# mp3_Breakout.net
KiCad netlist of a schematic drawn in EAGLE
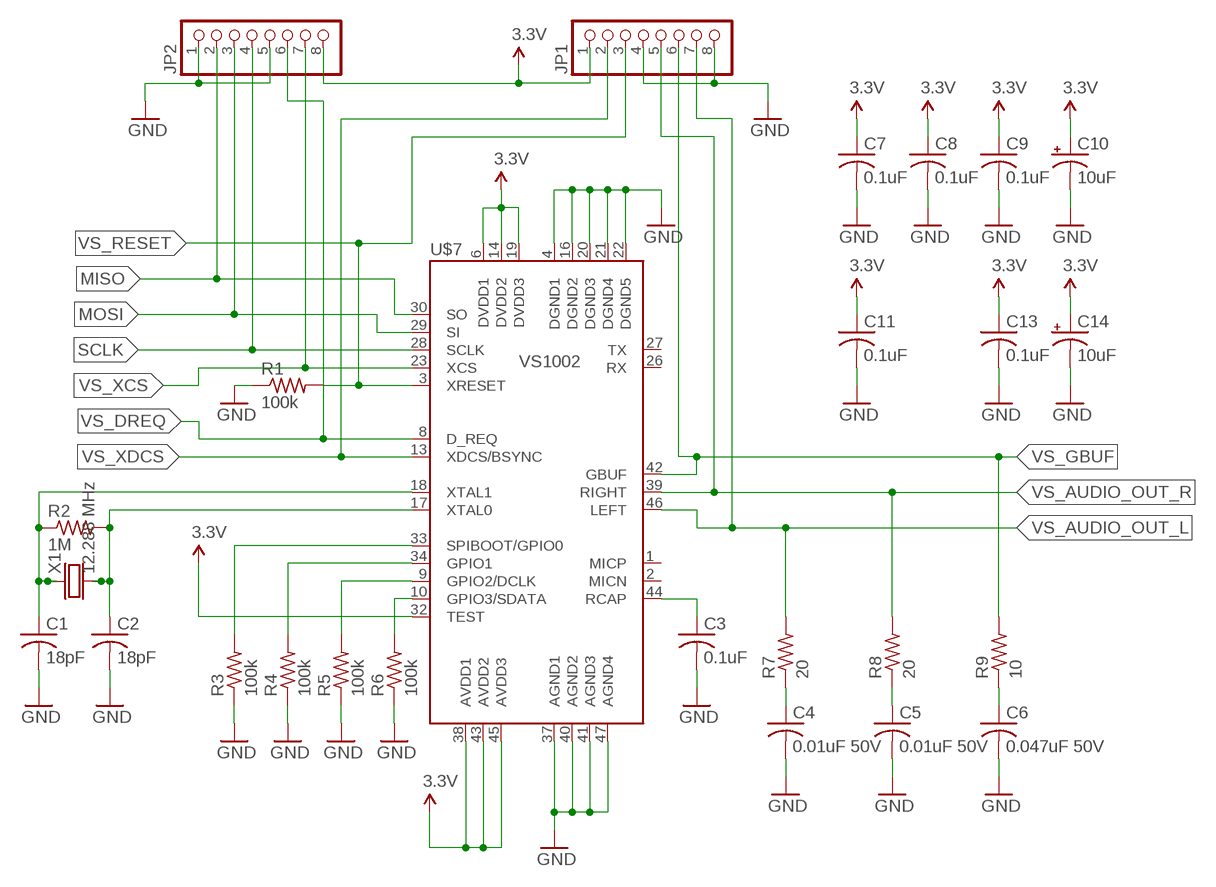
[diagram p0: schematic, sheet 1]

(export (version "E")
  (design (tool "Eeschema 10.0.6"))
  (components
    (comp (ref "C1")
      (value "18pF")
      (footprint "eagle-import:0603_RESISTOR")
      (libsource (lib "eagle-import") (part "0603_CAP"))
    )
    (comp (ref "C2")
      (value "18pF")
      (footprint "eagle-import:0603_RESISTOR")
      (libsource (lib "eagle-import") (part "0603_CAP"))
    )
    (comp (ref "C3")
      (value "0.1uF")
      (footprint "eagle-import:0603_RESISTOR")
      (libsource (lib "eagle-import") (part "0603_CAP"))
    )
    (comp (ref "C4")
      (value "0.01uF 50V")
      (footprint "eagle-import:0603_RESISTOR")
      (libsource (lib "eagle-import") (part "0603_CAP"))
    )
    (comp (ref "C5")
      (value "0.01uF 50V")
      (footprint "eagle-import:0603_RESISTOR")
      (libsource (lib "eagle-import") (part "0603_CAP"))
    )
    (comp (ref "C6")
      (value "0.047uF 50V")
      (footprint "eagle-import:0603_RESISTOR")
      (libsource (lib "eagle-import") (part "0603_CAP"))
    )
    (comp (ref "C7")
      (value "0.1uF")
      (footprint "eagle-import:0603_RESISTOR")
      (libsource (lib "eagle-import") (part "0603_CAP"))
    )
    (comp (ref "C8")
      (value "0.1uF")
      (footprint "eagle-import:0603_RESISTOR")
      (libsource (lib "eagle-import") (part "0603_CAP"))
    )
    (comp (ref "C9")
      (value "0.1uF")
      (footprint "eagle-import:0603_RESISTOR")
      (libsource (lib "eagle-import") (part "0603_CAP"))
    )
    (comp (ref "C10")
      (value "10uF")
      (footprint "eagle-import:CAP_B")
      (libsource (lib "eagle-import") (part "CAP_POL_B"))
    )
    (comp (ref "C11")
      (value "0.1uF")
      (footprint "eagle-import:0603_RESISTOR")
      (libsource (lib "eagle-import") (part "0603_CAP"))
    )
    (comp (ref "C13")
      (value "0.1uF")
      (footprint "eagle-import:0603_RESISTOR")
      (libsource (lib "eagle-import") (part "0603_CAP"))
    )
    (comp (ref "C14")
      (value "10uF")
      (footprint "eagle-import:CAP_B")
      (libsource (lib "eagle-import") (part "CAP_POL_B"))
    )
    (comp (ref "JP1")
      (value "PINHD-1X8")
      (footprint "eagle-import:1X08")
      (libsource (lib "eagle-import") (part "PINHD-1X8"))
    )
    (comp (ref "JP2")
      (value "PINHD-1X8")
      (footprint "eagle-import:1X08")
      (libsource (lib "eagle-import") (part "PINHD-1X8"))
    )
    (comp (ref "R1")
      (value "100k")
      (footprint "eagle-import:0603_RESISTOR")
      (libsource (lib "eagle-import") (part "0603_RESISTOR"))
    )
    (comp (ref "R2")
      (value "1M")
      (footprint "eagle-import:0603_RESISTOR")
      (libsource (lib "eagle-import") (part "0603_RESISTOR"))
    )
    (comp (ref "R3")
      (value "100k")
      (footprint "eagle-import:0603_RESISTOR")
      (libsource (lib "eagle-import") (part "0603_RESISTOR"))
    )
    (comp (ref "R4")
      (value "100k")
      (footprint "eagle-import:0603_RESISTOR")
      (libsource (lib "eagle-import") (part "0603_RESISTOR"))
    )
    (comp (ref "R5")
      (value "100k")
      (footprint "eagle-import:0603_RESISTOR")
      (libsource (lib "eagle-import") (part "0603_RESISTOR"))
    )
    (comp (ref "R6")
      (value "100k")
      (footprint "eagle-import:0603_RESISTOR")
      (libsource (lib "eagle-import") (part "0603_RESISTOR"))
    )
    (comp (ref "R7")
      (value "20")
      (footprint "eagle-import:0603_RESISTOR")
      (libsource (lib "eagle-import") (part "0603_RESISTOR"))
    )
    (comp (ref "R8")
      (value "20")
      (footprint "eagle-import:0603_RESISTOR")
      (libsource (lib "eagle-import") (part "0603_RESISTOR"))
    )
    (comp (ref "R9")
      (value "10")
      (footprint "eagle-import:0603_RESISTOR")
      (libsource (lib "eagle-import") (part "0603_RESISTOR"))
    )
    (comp (ref "U$7")
      (value "VS1002")
      (footprint "eagle-import:LQFP-48")
      (libsource (lib "eagle-import") (part "VS1002"))
    )
    (comp (ref "X1")
      (value "12.288 MHz")
      (footprint "eagle-import:CRYSTAL_5X3")
      (libsource (lib "eagle-import") (part "CRYSTAL_5X3"))
    )
  )
  (nets
    (net (code "1") (name "3.3V") (class "Default")
      (node (ref "C10") (pin "+") (pinfunction "+_+") (pintype "passive"))
      (node (ref "C11") (pin "1") (pinfunction "1_1") (pintype "passive"))
      (node (ref "C13") (pin "1") (pinfunction "1_1") (pintype "passive"))
      (node (ref "C14") (pin "+") (pinfunction "+_+") (pintype "passive"))
      (node (ref "C7") (pin "1") (pinfunction "1_1") (pintype "passive"))
      (node (ref "C8") (pin "1") (pinfunction "1_1") (pintype "passive"))
      (node (ref "C9") (pin "1") (pinfunction "1_1") (pintype "passive"))
      (node (ref "JP1") (pin "1") (pinfunction "1_1") (pintype "passive"))
      (node (ref "JP2") (pin "8") (pinfunction "8_8") (pintype "passive"))
      (node (ref "U$7") (pin "14") (pinfunction "DVDD2_14") (pintype "power_in"))
      (node (ref "U$7") (pin "19") (pinfunction "DVDD3_19") (pintype "power_in"))
      (node (ref "U$7") (pin "32") (pinfunction "TEST_32") (pintype "bidirectional"))
      (node (ref "U$7") (pin "38") (pinfunction "AVDD1_38") (pintype "power_in"))
      (node (ref "U$7") (pin "43") (pinfunction "AVDD2_43") (pintype "power_in"))
      (node (ref "U$7") (pin "45") (pinfunction "AVDD3_45") (pintype "power_in"))
      (node (ref "U$7") (pin "6") (pinfunction "DVDD1_6") (pintype "power_in"))
    )
    (net (code "2") (name "GND") (class "Default")
      (node (ref "C1") (pin "2") (pinfunction "2_2") (pintype "passive"))
      (node (ref "C10") (pin "-") (pinfunction "-_-") (pintype "passive"))
      (node (ref "C11") (pin "2") (pinfunction "2_2") (pintype "passive"))
      (node (ref "C13") (pin "2") (pinfunction "2_2") (pintype "passive"))
      (node (ref "C14") (pin "-") (pinfunction "-_-") (pintype "passive"))
      (node (ref "C2") (pin "2") (pinfunction "2_2") (pintype "passive"))
      (node (ref "C3") (pin "2") (pinfunction "2_2") (pintype "passive"))
      (node (ref "C4") (pin "2") (pinfunction "2_2") (pintype "passive"))
      (node (ref "C5") (pin "2") (pinfunction "2_2") (pintype "passive"))
      (node (ref "C6") (pin "2") (pinfunction "2_2") (pintype "passive"))
      (node (ref "C7") (pin "2") (pinfunction "2_2") (pintype "passive"))
      (node (ref "C8") (pin "2") (pinfunction "2_2") (pintype "passive"))
      (node (ref "C9") (pin "2") (pinfunction "2_2") (pintype "passive"))
      (node (ref "JP1") (pin "4") (pinfunction "4_4") (pintype "passive"))
      (node (ref "JP1") (pin "8") (pinfunction "8_8") (pintype "passive"))
      (node (ref "JP2") (pin "1") (pinfunction "1_1") (pintype "passive"))
      (node (ref "JP2") (pin "5") (pinfunction "5_5") (pintype "passive"))
      (node (ref "R1") (pin "1") (pinfunction "1_1") (pintype "passive"))
      (node (ref "R3") (pin "1") (pinfunction "1_1") (pintype "passive"))
      (node (ref "R4") (pin "1") (pinfunction "1_1") (pintype "passive"))
      (node (ref "R5") (pin "1") (pinfunction "1_1") (pintype "passive"))
      (node (ref "R6") (pin "1") (pinfunction "1_1") (pintype "passive"))
      (node (ref "U$7") (pin "16") (pinfunction "DGND2_16") (pintype "bidirectional"))
      (node (ref "U$7") (pin "20") (pinfunction "DGND3_20") (pintype "bidirectional"))
      (node (ref "U$7") (pin "21") (pinfunction "DGND4_21") (pintype "bidirectional"))
      (node (ref "U$7") (pin "22") (pinfunction "DGND5_22") (pintype "bidirectional"))
      (node (ref "U$7") (pin "37") (pinfunction "AGND1_37") (pintype "bidirectional"))
      (node (ref "U$7") (pin "4") (pinfunction "DGND1_4") (pintype "power_in"))
      (node (ref "U$7") (pin "40") (pinfunction "AGND2_40") (pintype "bidirectional"))
      (node (ref "U$7") (pin "41") (pinfunction "AGND3_41") (pintype "bidirectional"))
      (node (ref "U$7") (pin "47") (pinfunction "AGND4_47") (pintype "bidirectional"))
    )
    (net (code "3") (name "MISO") (class "Default")
      (node (ref "JP2") (pin "2") (pinfunction "2_2") (pintype "passive"))
      (node (ref "U$7") (pin "30") (pinfunction "SO_30") (pintype "bidirectional"))
    )
    (net (code "4") (name "MOSI") (class "Default")
      (node (ref "JP2") (pin "3") (pinfunction "3_3") (pintype "passive"))
      (node (ref "U$7") (pin "29") (pinfunction "SI_29") (pintype "bidirectional"))
    )
    (net (code "5") (name "Net-(C4-Pad1)") (class "Default")
      (node (ref "C4") (pin "1") (pinfunction "1_1") (pintype "passive"))
      (node (ref "R7") (pin "1") (pinfunction "1_1") (pintype "passive"))
    )
    (net (code "6") (name "Net-(C5-Pad1)") (class "Default")
      (node (ref "C5") (pin "1") (pinfunction "1_1") (pintype "passive"))
      (node (ref "R8") (pin "1") (pinfunction "1_1") (pintype "passive"))
    )
    (net (code "7") (name "Net-(C6-Pad1)") (class "Default")
      (node (ref "C6") (pin "1") (pinfunction "1_1") (pintype "passive"))
      (node (ref "R9") (pin "1") (pinfunction "1_1") (pintype "passive"))
    )
    (net (code "8") (name "Net-(U$7-GPIO1)") (class "Default")
      (node (ref "R4") (pin "2") (pinfunction "2_2") (pintype "passive"))
      (node (ref "U$7") (pin "34") (pinfunction "GPIO1_34") (pintype "bidirectional"))
    )
    (net (code "9") (name "Net-(U$7-GPIO2{slash}DCLK)") (class "Default")
      (node (ref "R5") (pin "2") (pinfunction "2_2") (pintype "passive"))
      (node (ref "U$7") (pin "9") (pinfunction "GPIO2/DCLK_9") (pintype "bidirectional"))
    )
    (net (code "10") (name "Net-(U$7-GPIO3{slash}SDATA)") (class "Default")
      (node (ref "R6") (pin "2") (pinfunction "2_2") (pintype "passive"))
      (node (ref "U$7") (pin "10") (pinfunction "GPIO3/SDATA_10") (pintype "bidirectional"))
    )
    (net (code "11") (name "Net-(U$7-RCAP)") (class "Default")
      (node (ref "C3") (pin "1") (pinfunction "1_1") (pintype "passive"))
      (node (ref "U$7") (pin "44") (pinfunction "RCAP_44") (pintype "bidirectional"))
    )
    (net (code "12") (name "Net-(U$7-SPIBOOT{slash}GPIO0)") (class "Default")
      (node (ref "R3") (pin "2") (pinfunction "2_2") (pintype "passive"))
      (node (ref "U$7") (pin "33") (pinfunction "SPIBOOT/GPIO0_33") (pintype "bidirectional"))
    )
    (net (code "13") (name "Net-(U$7-XTAL0)") (class "Default")
      (node (ref "C2") (pin "1") (pinfunction "1_1") (pintype "passive"))
      (node (ref "R2") (pin "2") (pinfunction "2_2") (pintype "passive"))
      (node (ref "U$7") (pin "17") (pinfunction "XTAL0_17") (pintype "bidirectional"))
      (node (ref "X1") (pin "2") (pinfunction "2_2") (pintype "passive"))
    )
    (net (code "14") (name "Net-(U$7-XTAL1)") (class "Default")
      (node (ref "C1") (pin "1") (pinfunction "1_1") (pintype "passive"))
      (node (ref "R2") (pin "1") (pinfunction "1_1") (pintype "passive"))
      (node (ref "U$7") (pin "18") (pinfunction "XTAL1_18") (pintype "bidirectional"))
      (node (ref "X1") (pin "1") (pinfunction "1_1") (pintype "passive"))
    )
    (net (code "15") (name "SCLK") (class "Default")
      (node (ref "JP2") (pin "4") (pinfunction "4_4") (pintype "passive"))
      (node (ref "U$7") (pin "28") (pinfunction "SCLK_28") (pintype "bidirectional"))
    )
    (net (code "16") (name "VS_AUDIO_OUT_L") (class "Default")
      (node (ref "JP1") (pin "7") (pinfunction "7_7") (pintype "passive"))
      (node (ref "R7") (pin "2") (pinfunction "2_2") (pintype "passive"))
      (node (ref "U$7") (pin "46") (pinfunction "LEFT_46") (pintype "bidirectional"))
    )
    (net (code "17") (name "VS_AUDIO_OUT_R") (class "Default")
      (node (ref "JP1") (pin "5") (pinfunction "5_5") (pintype "passive"))
      (node (ref "R8") (pin "2") (pinfunction "2_2") (pintype "passive"))
      (node (ref "U$7") (pin "39") (pinfunction "RIGHT_39") (pintype "bidirectional"))
    )
    (net (code "18") (name "VS_DREQ") (class "Default")
      (node (ref "JP2") (pin "6") (pinfunction "6_6") (pintype "passive"))
      (node (ref "U$7") (pin "8") (pinfunction "D_REQ_8") (pintype "bidirectional"))
    )
    (net (code "19") (name "VS_GBUF") (class "Default")
      (node (ref "JP1") (pin "6") (pinfunction "6_6") (pintype "passive"))
      (node (ref "R9") (pin "2") (pinfunction "2_2") (pintype "passive"))
      (node (ref "U$7") (pin "42") (pinfunction "GBUF_42") (pintype "bidirectional"))
    )
    (net (code "20") (name "VS_RESET") (class "Default")
      (node (ref "JP1") (pin "3") (pinfunction "3_3") (pintype "passive"))
      (node (ref "R1") (pin "2") (pinfunction "2_2") (pintype "passive"))
      (node (ref "U$7") (pin "3") (pinfunction "XRESET_3") (pintype "bidirectional"))
    )
    (net (code "21") (name "VS_XCS") (class "Default")
      (node (ref "JP2") (pin "7") (pinfunction "7_7") (pintype "passive"))
      (node (ref "U$7") (pin "23") (pinfunction "XCS_23") (pintype "bidirectional"))
    )
    (net (code "22") (name "VS_XDCS") (class "Default")
      (node (ref "JP1") (pin "2") (pinfunction "2_2") (pintype "passive"))
      (node (ref "U$7") (pin "13") (pinfunction "XDCS/BSYNC_13") (pintype "bidirectional"))
    )
    (net (code "23") (name "unconnected-(U$7-MICN-Pad2)") (class "Default")
      (node (ref "U$7") (pin "2") (pinfunction "MICN_2") (pintype "bidirectional"))
    )
    (net (code "24") (name "unconnected-(U$7-MICP-Pad1)") (class "Default")
      (node (ref "U$7") (pin "1") (pinfunction "MICP_1") (pintype "bidirectional"))
    )
    (net (code "25") (name "unconnected-(U$7-RX-Pad26)") (class "Default")
      (node (ref "U$7") (pin "26") (pinfunction "RX_26") (pintype "bidirectional"))
    )
    (net (code "26") (name "unconnected-(U$7-TX-Pad27)") (class "Default")
      (node (ref "U$7") (pin "27") (pinfunction "TX_27") (pintype "bidirectional"))
    )
  )
)
